# Nguyen_Ly.net
KiCad netlist of a schematic drawn in Altium Designer
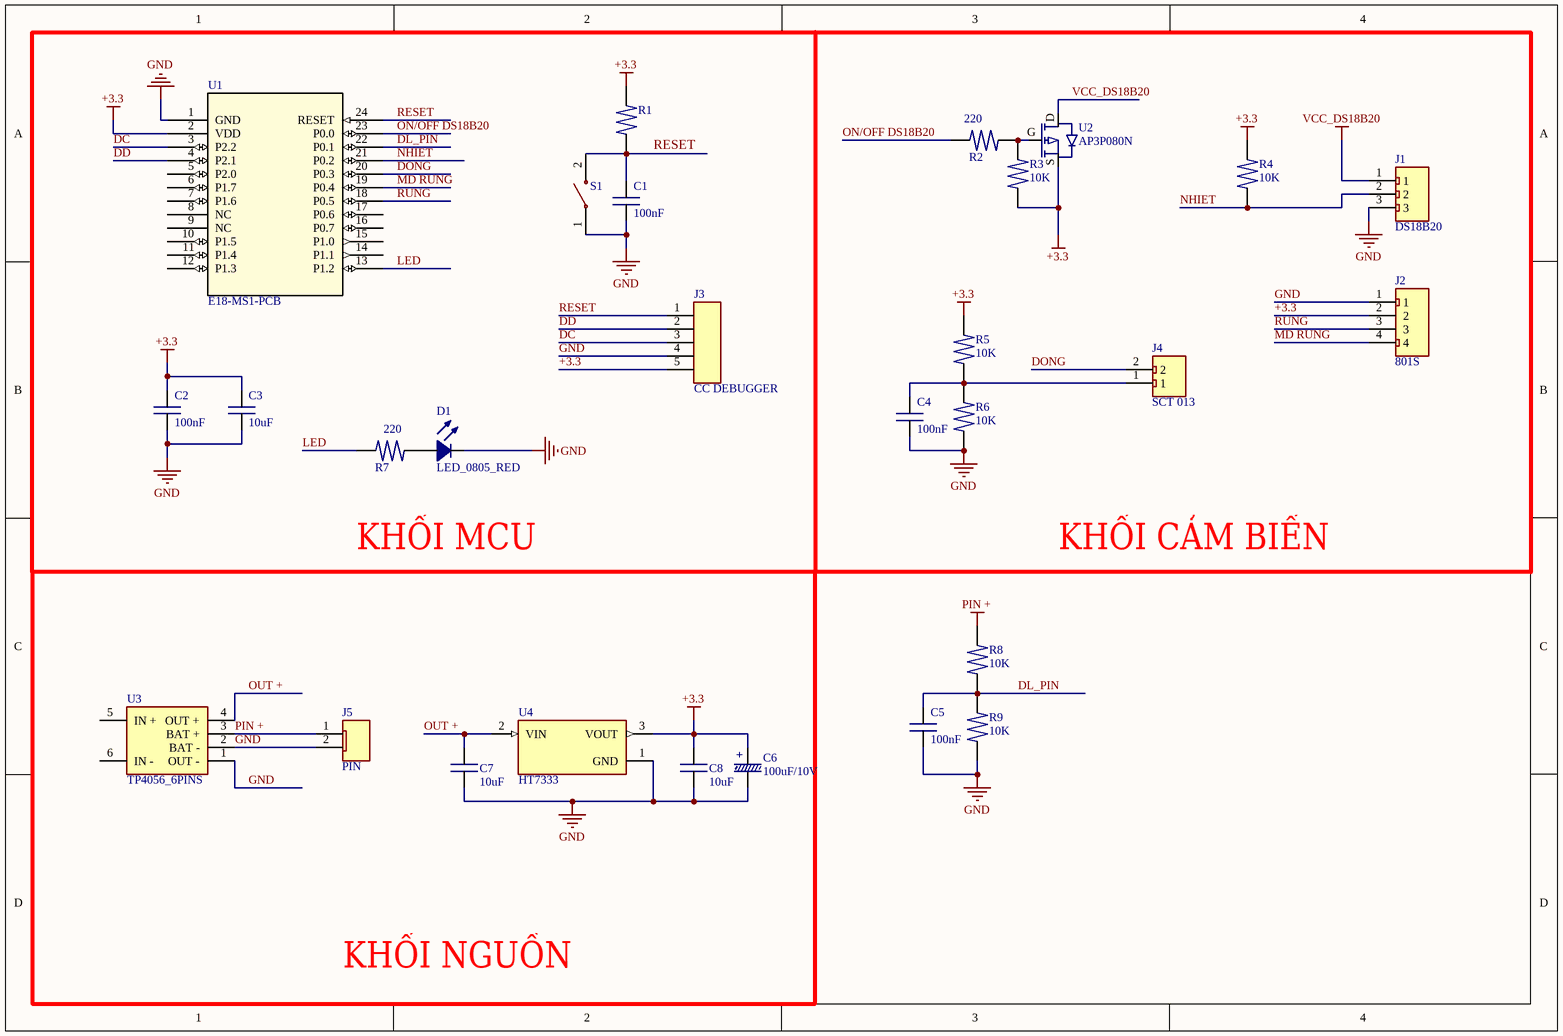
[diagram p0: Nguyen_Ly.SchDoc]

(export (version "E")
  (design (tool "Eeschema 10.0.6"))
  (components
    (comp (ref "C1")
      (value "100nF")
      (footprint "CAPACITOR 0805")
      (description "Generic Capacitor 0805, 2x1.25x1.4mm.")
      (libsource (lib "MyComponents") (part "CAPACITOR 0805"))
    )
    (comp (ref "C2")
      (value "100nF")
      (footprint "CAPACITOR 0805")
      (description "Generic Capacitor 0805, 2x1.25x1.4mm.")
      (libsource (lib "MyComponents") (part "CAPACITOR 0805"))
    )
    (comp (ref "C3")
      (value "10uF")
      (footprint "CAPACITOR 0805")
      (description "Generic Capacitor 0805, 2x1.25x1.4mm.")
      (libsource (lib "MyComponents") (part "CAPACITOR 0805"))
    )
    (comp (ref "C4")
      (value "100nF")
      (footprint "CAPACITOR 0805")
      (description "Generic Capacitor 0805, 2x1.25x1.4mm.")
      (libsource (lib "MyComponents") (part "CAPACITOR 0805"))
    )
    (comp (ref "C5")
      (value "100nF")
      (footprint "CAPACITOR 0805")
      (description "Generic Capacitor 0805, 2x1.25x1.4mm.")
      (libsource (lib "MyComponents") (part "CAPACITOR 0805"))
    )
    (comp (ref "C6")
      (value "100uF/10V")
      (footprint "ALUMINUM_5mm")
      (description "Aluminum Capacitor 100uF/10V 5mm")
      (libsource (lib "MyComponents") (part "100uF/10V"))
    )
    (comp (ref "C7")
      (value "10uF")
      (footprint "CAPACITOR 0805")
      (description "Generic Capacitor 0805, 2x1.25x1.4mm.")
      (libsource (lib "MyComponents") (part "CAPACITOR 0805"))
    )
    (comp (ref "C8")
      (value "10uF")
      (footprint "CAPACITOR 0805")
      (description "Generic Capacitor 0805, 2x1.25x1.4mm.")
      (libsource (lib "MyComponents") (part "CAPACITOR 0805"))
    )
    (comp (ref "D1")
      (value "LED_0805_RED")
      (footprint "LED_0805_RED")
      (description "LED 0805 Red.")
      (libsource (lib "MyComponents") (part "LED_0805_RED"))
    )
    (comp (ref "J1")
      (value "DS18B20")
      (footprint "BORNE-5.00-3P")
      (description "Borne 3 Vias, Pitch 5mm.")
      (libsource (lib "MyComponents") (part "BORNE-5.00-3P"))
    )
    (comp (ref "J2")
      (value "801S")
      (footprint "BORNE-5.00-4P")
      (description "Borne 4 Vias, Pitch 5mm.")
      (libsource (lib "MyComponents") (part "BORNE-5.00-4P"))
    )
    (comp (ref "J3")
      (value "CC DEBUGGER")
      (footprint "MALE-2.54-5P")
      (description "Male Header Connector 2.54mm 5 Pins.")
      (libsource (lib "MyComponents") (part "MALE-2.54-5P"))
    )
    (comp (ref "J4")
      (value "SCT 013")
      (footprint "BORNE-5.00-2P")
      (description "Borne 2 Vias, Pitch 5mm.")
      (libsource (lib "MyComponents") (part "BORNE-5.00-2P"))
    )
    (comp (ref "J5")
      (value "PIN")
      (footprint "JST-2.54-2P")
      (description "Female Connector JST 2 Vias, 2.54mm.")
      (libsource (lib "MyComponents") (part "JST-2.54-2P"))
    )
    (comp (ref "R1")
      (value "RESISTOR_0805")
      (footprint "RESISTOR_0805")
      (description "Generic Resistor 0805.")
      (libsource (lib "MyComponents") (part "RESISTOR_0805"))
    )
    (comp (ref "R2")
      (value "220")
      (footprint "RESISTOR_0805")
      (description "Generic Resistor 0805.")
      (libsource (lib "MyComponents") (part "RESISTOR_0805"))
    )
    (comp (ref "R3")
      (value "10K")
      (footprint "RESISTOR_0805")
      (description "Generic Resistor 0805.")
      (libsource (lib "MyComponents") (part "RESISTOR_0805"))
    )
    (comp (ref "R4")
      (value "10K")
      (footprint "RESISTOR_0805")
      (description "Generic Resistor 0805.")
      (libsource (lib "MyComponents") (part "RESISTOR_0805"))
    )
    (comp (ref "R5")
      (value "10K")
      (footprint "RESISTOR_0805")
      (description "Generic Resistor 0805.")
      (libsource (lib "MyComponents") (part "RESISTOR_0805"))
    )
    (comp (ref "R6")
      (value "10K")
      (footprint "RESISTOR_0805")
      (description "Generic Resistor 0805.")
      (libsource (lib "MyComponents") (part "RESISTOR_0805"))
    )
    (comp (ref "R7")
      (value "220")
      (footprint "RESISTOR_0805")
      (description "Generic Resistor 0805.")
      (libsource (lib "MyComponents") (part "RESISTOR_0805"))
    )
    (comp (ref "R8")
      (value "10K")
      (footprint "RESISTOR_0805")
      (description "Generic Resistor 0805.")
      (libsource (lib "MyComponents") (part "RESISTOR_0805"))
    )
    (comp (ref "R9")
      (value "10K")
      (footprint "RESISTOR_0805")
      (description "Generic Resistor 0805.")
      (libsource (lib "MyComponents") (part "RESISTOR_0805"))
    )
    (comp (ref "S1")
      (value "PUSH_BUTTON_SMD_3X4X2")
      (footprint "PUSH_BUTTON_SMD_3X4X2")
      (description "Push Button Tactile Switch SMD 2 Pins 3x4x2mm.")
      (libsource (lib "MyComponents") (part "PUSH_BUTTON_SMD_3X4X2"))
    )
    (comp (ref "U1")
      (value "E18-MS1-PCB")
      (footprint "E18-MS1-PCB_BYT")
      (description "No Description Available")
      (fields (field (name "COPYRIGHT") "Copyright (C) 2026 Ultra Librarian. All rights reserved."))
      (libsource (lib "Integrated_Library1") (part "E18-MS1-PCB"))
    )
    (comp (ref "U2")
      (value "AP3P080N")
      (footprint "SOT23-3")
      (description "Mosfet PNP")
      (libsource (lib "MyComponents") (part "AP3P080N"))
    )
    (comp (ref "U3")
      (value "TP4056_6PINS")
      (footprint "TP4056_6PINs")
      (description "MODULE BATTERY CHARGER 6 PINS")
      (libsource (lib "MyComponents") (part "TP4056_6PINS"))
    )
    (comp (ref "U4")
      (value "HT7333")
      (footprint "IC_HT7333")
      (description "Three-terminal, low power, high voltage regulator implemented in CMOS technology")
      (fields (field (name "MF") "Holtek Semiconductor"))
      (libsource (lib "HT7333") (part "HT7333"))
    )
  )
  (nets
    (net (code "1") (name "+3.3") (class "Default")
      (node (ref "C2") (pin "2") (pinfunction "2_2") (pintype "passive"))
      (node (ref "C3") (pin "2") (pinfunction "2_2") (pintype "passive"))
      (node (ref "C6") (pin "1") (pinfunction "1_1") (pintype "passive"))
      (node (ref "C8") (pin "2") (pinfunction "2_2") (pintype "passive"))
      (node (ref "J2") (pin "2") (pinfunction "2_2") (pintype "passive"))
      (node (ref "J3") (pin "5") (pintype "passive"))
      (node (ref "R1") (pin "2") (pinfunction "2_2") (pintype "passive"))
      (node (ref "R3") (pin "1") (pinfunction "1_1") (pintype "passive"))
      (node (ref "R4") (pin "2") (pinfunction "2_2") (pintype "passive"))
      (node (ref "R5") (pin "2") (pinfunction "2_2") (pintype "passive"))
      (node (ref "U1") (pin "2") (pinfunction "VDD_2") (pintype "power_in"))
      (node (ref "U2") (pin "S") (pinfunction "S_S") (pintype "passive"))
      (node (ref "U4") (pin "3") (pinfunction "VOUT_3") (pintype "output"))
    )
    (net (code "2") (name "/DC") (class "Default")
      (node (ref "J3") (pin "3") (pintype "passive"))
      (node (ref "U1") (pin "3") (pinfunction "P2.2_3") (pintype "bidirectional"))
    )
    (net (code "3") (name "/DD") (class "Default")
      (node (ref "J3") (pin "2") (pintype "passive"))
      (node (ref "U1") (pin "4") (pinfunction "P2.1_4") (pintype "bidirectional"))
    )
    (net (code "4") (name "/DL_PIN") (class "Default")
      (node (ref "C5") (pin "2") (pinfunction "2_2") (pintype "passive"))
      (node (ref "R8") (pin "1") (pinfunction "1_1") (pintype "passive"))
      (node (ref "R9") (pin "2") (pinfunction "2_2") (pintype "passive"))
      (node (ref "U1") (pin "22") (pinfunction "P0.1_22") (pintype "bidirectional"))
    )
    (net (code "5") (name "/DONG") (class "Default")
      (node (ref "J4") (pin "2") (pinfunction "2_2") (pintype "passive"))
      (node (ref "U1") (pin "20") (pinfunction "P0.3_20") (pintype "bidirectional"))
    )
    (net (code "6") (name "/LED") (class "Default")
      (node (ref "R7") (pin "2") (pinfunction "2_2") (pintype "passive"))
      (node (ref "U1") (pin "13") (pinfunction "P1.2_13") (pintype "bidirectional"))
    )
    (net (code "7") (name "/MD RUNG") (class "Default")
      (node (ref "J2") (pin "4") (pinfunction "4_4") (pintype "passive"))
      (node (ref "U1") (pin "19") (pinfunction "P0.4_19") (pintype "bidirectional"))
    )
    (net (code "8") (name "/NHIET") (class "Default")
      (node (ref "J1") (pin "2") (pinfunction "2_2") (pintype "passive"))
      (node (ref "R4") (pin "1") (pinfunction "1_1") (pintype "passive"))
      (node (ref "U1") (pin "21") (pinfunction "P0.2_21") (pintype "bidirectional"))
    )
    (net (code "9") (name "/ON{slash}OFF DS18B20") (class "Default")
      (node (ref "R2") (pin "2") (pinfunction "2_2") (pintype "passive"))
      (node (ref "U1") (pin "23") (pinfunction "P0.0_23") (pintype "bidirectional"))
    )
    (net (code "10") (name "/OUT +") (class "Default")
      (node (ref "C7") (pin "2") (pinfunction "2_2") (pintype "passive"))
      (node (ref "U3") (pin "4") (pinfunction "OUT_+_4") (pintype "passive"))
      (node (ref "U4") (pin "2") (pinfunction "VIN_2") (pintype "input"))
    )
    (net (code "11") (name "/RESET") (class "Default")
      (node (ref "C1") (pin "2") (pinfunction "2_2") (pintype "passive"))
      (node (ref "J3") (pin "1") (pintype "passive"))
      (node (ref "R1") (pin "1") (pinfunction "1_1") (pintype "passive"))
      (node (ref "S1") (pin "2") (pinfunction "2_2") (pintype "passive"))
      (node (ref "U1") (pin "24") (pinfunction "RESET_24") (pintype "input"))
    )
    (net (code "12") (name "/RUNG") (class "Default")
      (node (ref "J2") (pin "3") (pinfunction "3_3") (pintype "passive"))
      (node (ref "U1") (pin "18") (pinfunction "P0.5_18") (pintype "bidirectional"))
    )
    (net (code "13") (name "GND") (class "Default")
      (node (ref "C1") (pin "1") (pinfunction "1_1") (pintype "passive"))
      (node (ref "C2") (pin "1") (pinfunction "1_1") (pintype "passive"))
      (node (ref "C3") (pin "1") (pinfunction "1_1") (pintype "passive"))
      (node (ref "C4") (pin "1") (pinfunction "1_1") (pintype "passive"))
      (node (ref "C5") (pin "1") (pinfunction "1_1") (pintype "passive"))
      (node (ref "C6") (pin "2") (pinfunction "2_2") (pintype "passive"))
      (node (ref "C7") (pin "1") (pinfunction "1_1") (pintype "passive"))
      (node (ref "C8") (pin "1") (pinfunction "1_1") (pintype "passive"))
      (node (ref "D1") (pin "2") (pinfunction "2_2") (pintype "passive"))
      (node (ref "J1") (pin "3") (pinfunction "3_3") (pintype "passive"))
      (node (ref "J2") (pin "1") (pinfunction "1_1") (pintype "passive"))
      (node (ref "J3") (pin "4") (pintype "passive"))
      (node (ref "J5") (pin "2") (pintype "passive"))
      (node (ref "R6") (pin "1") (pinfunction "1_1") (pintype "passive"))
      (node (ref "R9") (pin "1") (pinfunction "1_1") (pintype "passive"))
      (node (ref "S1") (pin "1") (pinfunction "1_1") (pintype "passive"))
      (node (ref "U1") (pin "1") (pinfunction "GND_1") (pintype "power_in"))
      (node (ref "U3") (pin "1") (pinfunction "OUT_-_1") (pintype "passive"))
      (node (ref "U3") (pin "2") (pinfunction "BAT_-_2") (pintype "passive"))
      (node (ref "U4") (pin "1") (pinfunction "GND_1") (pintype "power_in"))
    )
    (net (code "14") (name "Net-(C4-Pad2)") (class "Default")
      (node (ref "C4") (pin "2") (pinfunction "2_2") (pintype "passive"))
      (node (ref "J4") (pin "1") (pinfunction "1_1") (pintype "passive"))
      (node (ref "R5") (pin "1") (pinfunction "1_1") (pintype "passive"))
      (node (ref "R6") (pin "2") (pinfunction "2_2") (pintype "passive"))
    )
    (net (code "15") (name "Net-(D1-Pad1)") (class "Default")
      (node (ref "D1") (pin "1") (pinfunction "1_1") (pintype "passive"))
      (node (ref "R7") (pin "1") (pinfunction "1_1") (pintype "passive"))
    )
    (net (code "16") (name "Net-(R2-Pad1)") (class "Default")
      (node (ref "R2") (pin "1") (pinfunction "1_1") (pintype "passive"))
      (node (ref "R3") (pin "2") (pinfunction "2_2") (pintype "passive"))
      (node (ref "U2") (pin "G") (pinfunction "G_G") (pintype "passive"))
    )
    (net (code "17") (name "PIN +") (class "Default")
      (node (ref "J5") (pin "1") (pintype "passive"))
      (node (ref "R8") (pin "2") (pinfunction "2_2") (pintype "passive"))
      (node (ref "U3") (pin "3") (pinfunction "BAT_+_3") (pintype "passive"))
    )
    (net (code "18") (name "VCC_DS18B20") (class "Default")
      (node (ref "J1") (pin "1") (pinfunction "1_1") (pintype "passive"))
      (node (ref "U2") (pin "D") (pinfunction "D_D") (pintype "passive"))
    )
    (net (code "19") (name "unconnected-(U1-NC-Pad8)") (class "Default")
      (node (ref "U1") (pin "8") (pinfunction "NC_8") (pintype "passive"))
    )
    (net (code "20") (name "unconnected-(U1-NC-Pad9)") (class "Default")
      (node (ref "U1") (pin "9") (pinfunction "NC_9") (pintype "passive"))
    )
    (net (code "21") (name "unconnected-(U1-P0.6-Pad17)") (class "Default")
      (node (ref "U1") (pin "17") (pinfunction "P0.6_17") (pintype "bidirectional"))
    )
    (net (code "22") (name "unconnected-(U1-P0.7-Pad16)") (class "Default")
      (node (ref "U1") (pin "16") (pinfunction "P0.7_16") (pintype "bidirectional"))
    )
    (net (code "23") (name "unconnected-(U1-P1.0-Pad15)") (class "Default")
      (node (ref "U1") (pin "15") (pinfunction "P1.0_15") (pintype "output"))
    )
    (net (code "24") (name "unconnected-(U1-P1.1-Pad14)") (class "Default")
      (node (ref "U1") (pin "14") (pinfunction "P1.1_14") (pintype "output"))
    )
    (net (code "25") (name "unconnected-(U1-P1.3-Pad12)") (class "Default")
      (node (ref "U1") (pin "12") (pinfunction "P1.3_12") (pintype "bidirectional"))
    )
    (net (code "26") (name "unconnected-(U1-P1.4-Pad11)") (class "Default")
      (node (ref "U1") (pin "11") (pinfunction "P1.4_11") (pintype "bidirectional"))
    )
    (net (code "27") (name "unconnected-(U1-P1.5-Pad10)") (class "Default")
      (node (ref "U1") (pin "10") (pinfunction "P1.5_10") (pintype "bidirectional"))
    )
    (net (code "28") (name "unconnected-(U1-P1.6-Pad7)") (class "Default")
      (node (ref "U1") (pin "7") (pinfunction "P1.6_7") (pintype "bidirectional"))
    )
    (net (code "29") (name "unconnected-(U1-P1.7-Pad6)") (class "Default")
      (node (ref "U1") (pin "6") (pinfunction "P1.7_6") (pintype "bidirectional"))
    )
    (net (code "30") (name "unconnected-(U1-P2.0-Pad5)") (class "Default")
      (node (ref "U1") (pin "5") (pinfunction "P2.0_5") (pintype "bidirectional"))
    )
    (net (code "31") (name "unconnected-(U3-IN_+-Pad5)") (class "Default")
      (node (ref "U3") (pin "5") (pinfunction "IN_+_5") (pintype "passive"))
    )
    (net (code "32") (name "unconnected-(U3-IN_--Pad6)") (class "Default")
      (node (ref "U3") (pin "6") (pinfunction "IN_-_6") (pintype "passive"))
    )
  )
)
